# CLK_HMC7044.net
KiCad netlist of a schematic drawn in Altium Designer
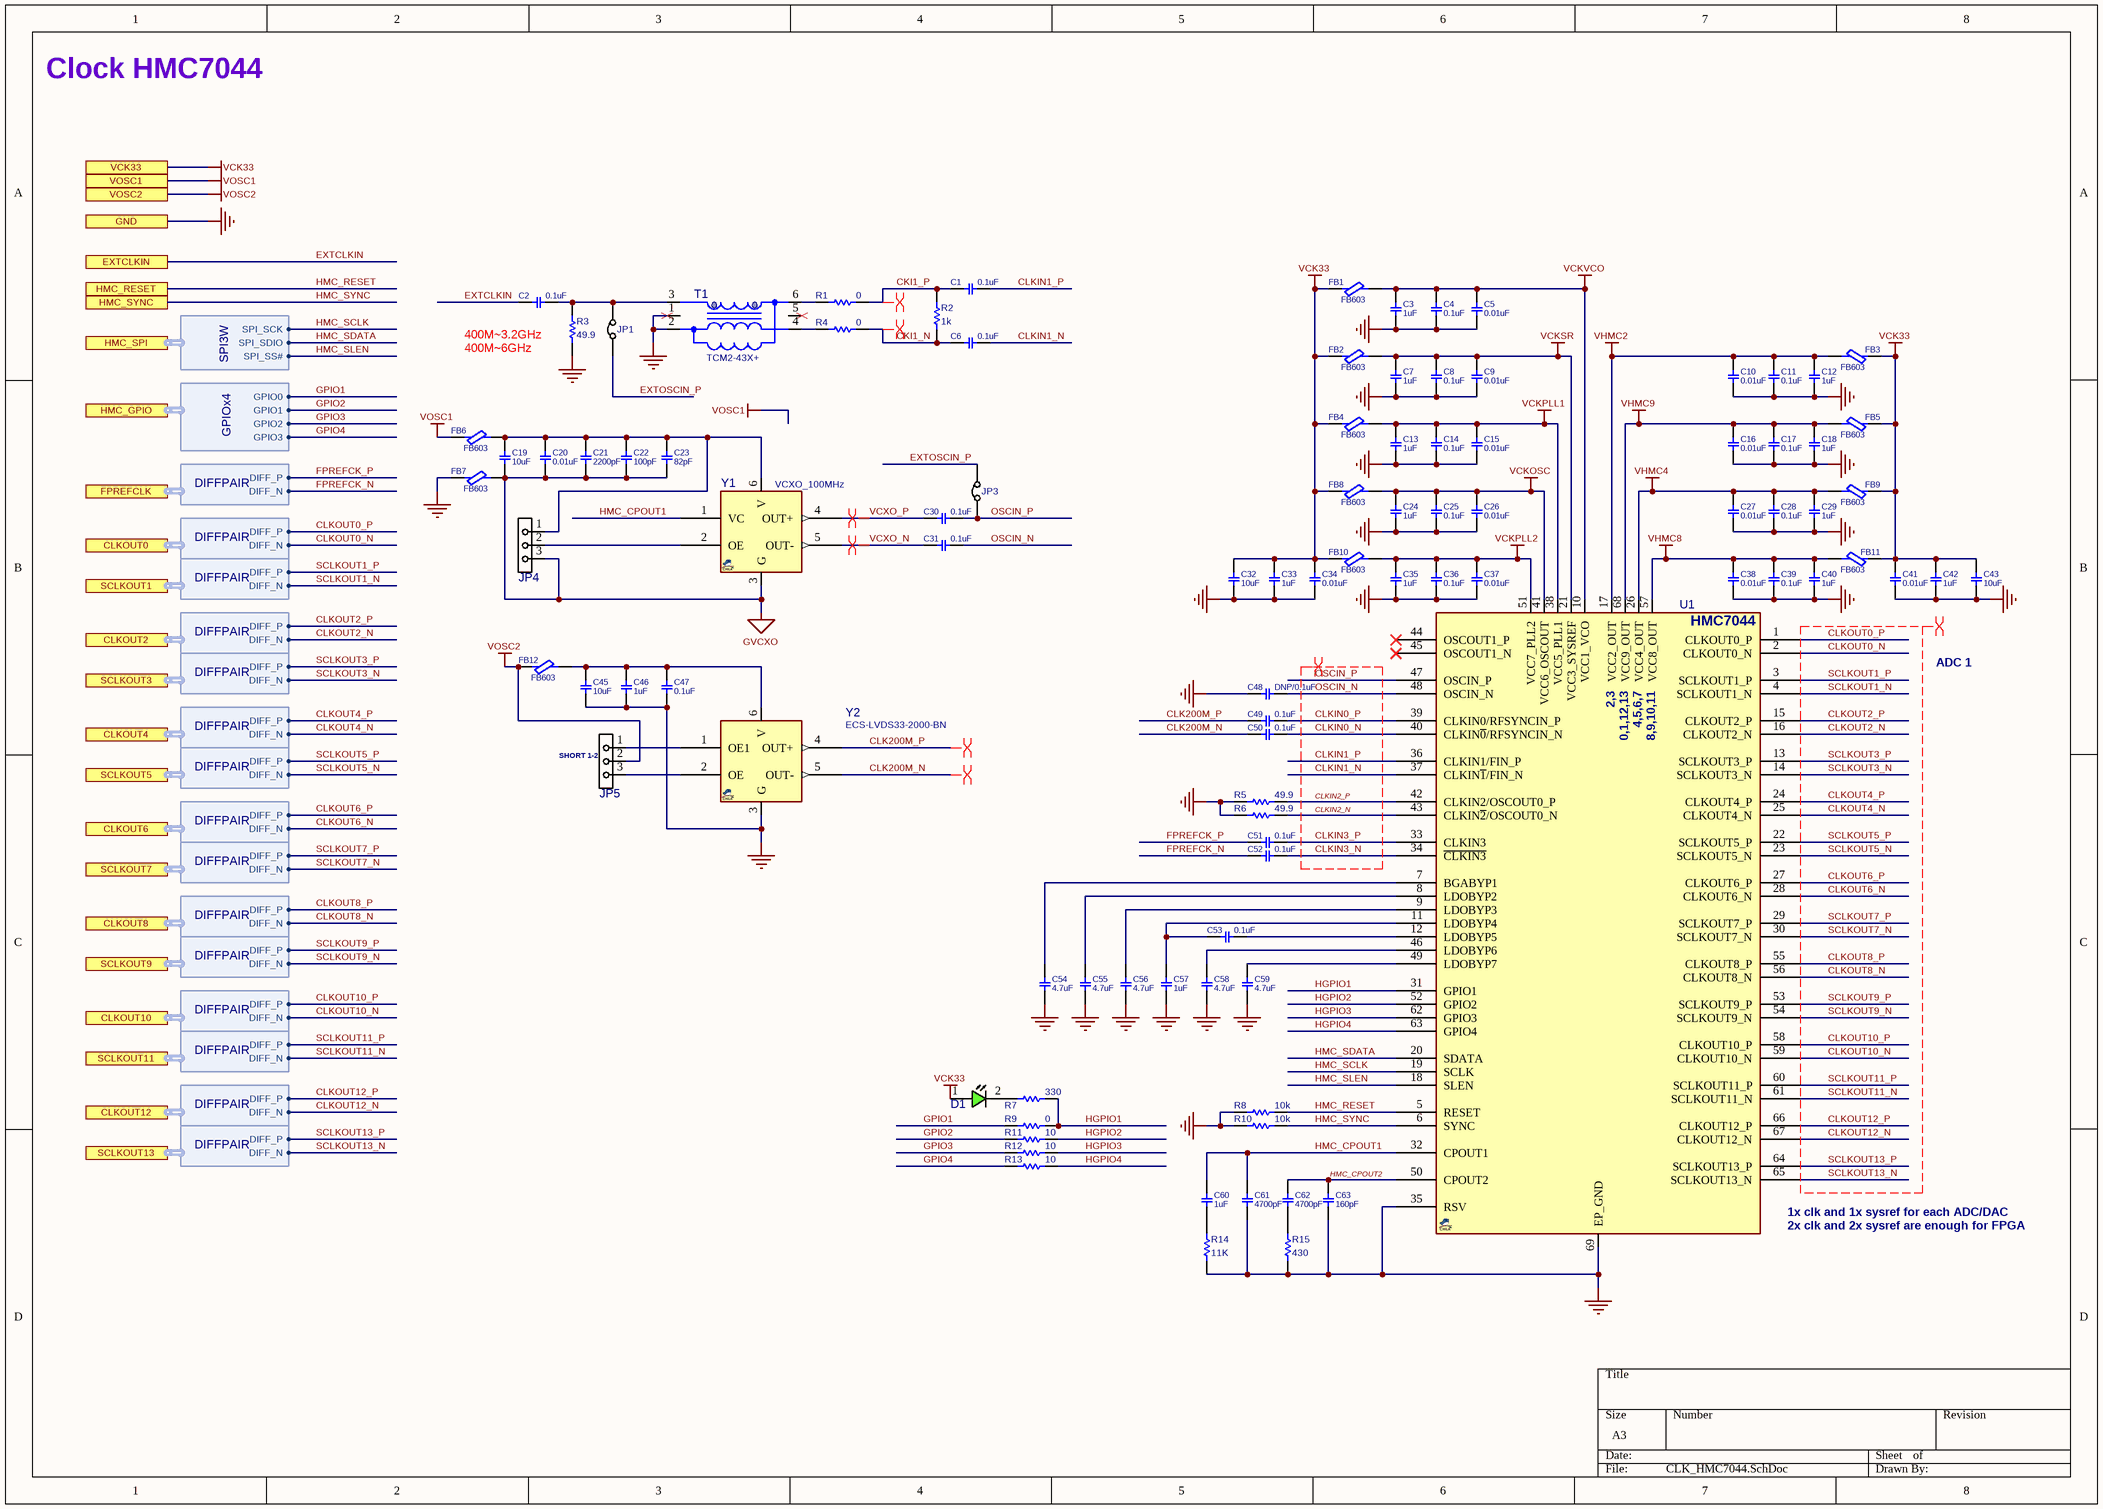
[diagram p0: CLK_HMC7044.SchDoc]

(export (version "E")
  (design (tool "Eeschema 10.0.6"))
  (components
    (comp (ref "C1")
      (value "0.1uF")
      (footprint "C0402")
      (description "CAP, MLCC")
      (libsource (lib "mlcc_smd_passive") (part "CAP_SMD_MLCC_100n50T"))
    )
    (comp (ref "C2")
      (value "0.1uF")
      (footprint "C0402")
      (description "CAP, MLCC")
      (libsource (lib "mlcc_smd_passive") (part "CAP_SMD_MLCC_100n50T"))
    )
    (comp (ref "C3")
      (value "1uF")
      (footprint "C0402")
      (description "CAP, MLCC")
      (libsource (lib "mlcc_smd_passive") (part "CAP_SMD_MLCC_100n50T"))
    )
    (comp (ref "C4")
      (value "0.1uF")
      (footprint "C0402")
      (description "CAP, MLCC")
      (libsource (lib "mlcc_smd_passive") (part "CAP_SMD_MLCC_100n50T"))
    )
    (comp (ref "C5")
      (value "0.01uF")
      (footprint "C0402")
      (description "CAP, MLCC")
      (libsource (lib "mlcc_smd_passive") (part "CAP_SMD_MLCC_100n50T"))
    )
    (comp (ref "C6")
      (value "0.1uF")
      (footprint "C0402")
      (description "CAP, MLCC")
      (libsource (lib "mlcc_smd_passive") (part "CAP_SMD_MLCC_100n50T"))
    )
    (comp (ref "C7")
      (value "1uF")
      (footprint "C0402")
      (description "CAP, MLCC")
      (libsource (lib "mlcc_smd_passive") (part "CAP_SMD_MLCC_100n50T"))
    )
    (comp (ref "C8")
      (value "0.1uF")
      (footprint "C0402")
      (description "CAP, MLCC")
      (libsource (lib "mlcc_smd_passive") (part "CAP_SMD_MLCC_100n50T"))
    )
    (comp (ref "C9")
      (value "0.01uF")
      (footprint "C0402")
      (description "CAP, MLCC")
      (libsource (lib "mlcc_smd_passive") (part "CAP_SMD_MLCC_100n50T"))
    )
    (comp (ref "C10")
      (value "0.01uF")
      (footprint "C0402")
      (description "CAP, MLCC")
      (libsource (lib "mlcc_smd_passive") (part "CAP_SMD_MLCC_100n50T"))
    )
    (comp (ref "C11")
      (value "0.1uF")
      (footprint "C0402")
      (description "CAP, MLCC")
      (libsource (lib "mlcc_smd_passive") (part "CAP_SMD_MLCC_100n50T"))
    )
    (comp (ref "C12")
      (value "1uF")
      (footprint "C0402")
      (description "CAP, MLCC")
      (libsource (lib "mlcc_smd_passive") (part "CAP_SMD_MLCC_100n50T"))
    )
    (comp (ref "C13")
      (value "1uF")
      (footprint "C0402")
      (description "CAP, MLCC")
      (libsource (lib "mlcc_smd_passive") (part "CAP_SMD_MLCC_100n50T"))
    )
    (comp (ref "C14")
      (value "0.1uF")
      (footprint "C0402")
      (description "CAP, MLCC")
      (libsource (lib "mlcc_smd_passive") (part "CAP_SMD_MLCC_100n50T"))
    )
    (comp (ref "C15")
      (value "0.01uF")
      (footprint "C0402")
      (description "CAP, MLCC")
      (libsource (lib "mlcc_smd_passive") (part "CAP_SMD_MLCC_100n50T"))
    )
    (comp (ref "C16")
      (value "0.01uF")
      (footprint "C0402")
      (description "CAP, MLCC")
      (libsource (lib "mlcc_smd_passive") (part "CAP_SMD_MLCC_100n50T"))
    )
    (comp (ref "C17")
      (value "0.1uF")
      (footprint "C0402")
      (description "CAP, MLCC")
      (libsource (lib "mlcc_smd_passive") (part "CAP_SMD_MLCC_100n50T"))
    )
    (comp (ref "C18")
      (value "1uF")
      (footprint "C0402")
      (description "CAP, MLCC")
      (libsource (lib "mlcc_smd_passive") (part "CAP_SMD_MLCC_100n50T"))
    )
    (comp (ref "C19")
      (value "10uF")
      (footprint "C0402")
      (description "CAP, MLCC")
      (libsource (lib "mlcc_smd_passive") (part "CAP_SMD_MLCC_100n50T"))
    )
    (comp (ref "C20")
      (value "0.01uF")
      (footprint "C0402")
      (description "CAP, MLCC")
      (libsource (lib "mlcc_smd_passive") (part "CAP_SMD_MLCC_100n50T"))
    )
    (comp (ref "C21")
      (value "2200pF")
      (footprint "C0402")
      (description "CAP, MLCC")
      (libsource (lib "mlcc_smd_passive") (part "CAP_SMD_MLCC_100n50T"))
    )
    (comp (ref "C22")
      (value "100pF")
      (footprint "C0402")
      (description "CAP, MLCC")
      (libsource (lib "mlcc_smd_passive") (part "CAP_SMD_MLCC_100n50T"))
    )
    (comp (ref "C23")
      (value "82pF")
      (footprint "C0402")
      (description "CAP, MLCC")
      (libsource (lib "mlcc_smd_passive") (part "CAP_SMD_MLCC_100n50T"))
    )
    (comp (ref "C24")
      (value "1uF")
      (footprint "C0402")
      (description "CAP, MLCC")
      (libsource (lib "mlcc_smd_passive") (part "CAP_SMD_MLCC_100n50T"))
    )
    (comp (ref "C25")
      (value "0.1uF")
      (footprint "C0402")
      (description "CAP, MLCC")
      (libsource (lib "mlcc_smd_passive") (part "CAP_SMD_MLCC_100n50T"))
    )
    (comp (ref "C26")
      (value "0.01uF")
      (footprint "C0402")
      (description "CAP, MLCC")
      (libsource (lib "mlcc_smd_passive") (part "CAP_SMD_MLCC_100n50T"))
    )
    (comp (ref "C27")
      (value "0.01uF")
      (footprint "C0402")
      (description "CAP, MLCC")
      (libsource (lib "mlcc_smd_passive") (part "CAP_SMD_MLCC_100n50T"))
    )
    (comp (ref "C28")
      (value "0.1uF")
      (footprint "C0402")
      (description "CAP, MLCC")
      (libsource (lib "mlcc_smd_passive") (part "CAP_SMD_MLCC_100n50T"))
    )
    (comp (ref "C29")
      (value "1uF")
      (footprint "C0402")
      (description "CAP, MLCC")
      (libsource (lib "mlcc_smd_passive") (part "CAP_SMD_MLCC_100n50T"))
    )
    (comp (ref "C30")
      (value "0.1uF")
      (footprint "C0402")
      (description "CAP, MLCC")
      (libsource (lib "mlcc_smd_passive") (part "CAP_SMD_MLCC_100n50T"))
    )
    (comp (ref "C31")
      (value "0.1uF")
      (footprint "C0402")
      (description "CAP, MLCC")
      (libsource (lib "mlcc_smd_passive") (part "CAP_SMD_MLCC_100n50T"))
    )
    (comp (ref "C32")
      (value "10uF")
      (footprint "C0402")
      (description "CAP, MLCC")
      (libsource (lib "mlcc_smd_passive") (part "CAP_SMD_MLCC_100n50T"))
    )
    (comp (ref "C33")
      (value "1uF")
      (footprint "C0402")
      (description "CAP, MLCC")
      (libsource (lib "mlcc_smd_passive") (part "CAP_SMD_MLCC_100n50T"))
    )
    (comp (ref "C34")
      (value "0.01uF")
      (footprint "C0402")
      (description "CAP, MLCC")
      (libsource (lib "mlcc_smd_passive") (part "CAP_SMD_MLCC_100n50T"))
    )
    (comp (ref "C35")
      (value "1uF")
      (footprint "C0402")
      (description "CAP, MLCC")
      (libsource (lib "mlcc_smd_passive") (part "CAP_SMD_MLCC_100n50T"))
    )
    (comp (ref "C36")
      (value "0.1uF")
      (footprint "C0402")
      (description "CAP, MLCC")
      (libsource (lib "mlcc_smd_passive") (part "CAP_SMD_MLCC_100n50T"))
    )
    (comp (ref "C37")
      (value "0.01uF")
      (footprint "C0402")
      (description "CAP, MLCC")
      (libsource (lib "mlcc_smd_passive") (part "CAP_SMD_MLCC_100n50T"))
    )
    (comp (ref "C38")
      (value "0.01uF")
      (footprint "C0402")
      (description "CAP, MLCC")
      (libsource (lib "mlcc_smd_passive") (part "CAP_SMD_MLCC_100n50T"))
    )
    (comp (ref "C39")
      (value "0.1uF")
      (footprint "C0402")
      (description "CAP, MLCC")
      (libsource (lib "mlcc_smd_passive") (part "CAP_SMD_MLCC_100n50T"))
    )
    (comp (ref "C40")
      (value "1uF")
      (footprint "C0402")
      (description "CAP, MLCC")
      (libsource (lib "mlcc_smd_passive") (part "CAP_SMD_MLCC_100n50T"))
    )
    (comp (ref "C41")
      (value "0.01uF")
      (footprint "C0402")
      (description "CAP, MLCC")
      (libsource (lib "mlcc_smd_passive") (part "CAP_SMD_MLCC_100n50T"))
    )
    (comp (ref "C42")
      (value "1uF")
      (footprint "C0402")
      (description "CAP, MLCC")
      (libsource (lib "mlcc_smd_passive") (part "CAP_SMD_MLCC_100n50T"))
    )
    (comp (ref "C43")
      (value "10uF")
      (footprint "C0402")
      (description "CAP, MLCC")
      (libsource (lib "mlcc_smd_passive") (part "CAP_SMD_MLCC_100n50T"))
    )
    (comp (ref "C45")
      (value "10uF")
      (footprint "C0402")
      (description "CAP, MLCC")
      (libsource (lib "mlcc_smd_passive") (part "CAP_SMD_MLCC_100n50T"))
    )
    (comp (ref "C46")
      (value "1uF")
      (footprint "C0402")
      (description "CAP, MLCC")
      (libsource (lib "mlcc_smd_passive") (part "CAP_SMD_MLCC_100n50T"))
    )
    (comp (ref "C47")
      (value "0.1uF")
      (footprint "C0402")
      (description "CAP, MLCC")
      (libsource (lib "mlcc_smd_passive") (part "CAP_SMD_MLCC_100n50T"))
    )
    (comp (ref "C48")
      (value "DNP/0.1uF")
      (footprint "C0402")
      (description "CAP, MLCC")
      (libsource (lib "mlcc_smd_passive") (part "CAP_SMD_MLCC_100n50T"))
    )
    (comp (ref "C49")
      (value "0.1uF")
      (footprint "C0402")
      (description "CAP, MLCC")
      (libsource (lib "mlcc_smd_passive") (part "CAP_SMD_MLCC_100n50T"))
    )
    (comp (ref "C50")
      (value "0.1uF")
      (footprint "C0402")
      (description "CAP, MLCC")
      (libsource (lib "mlcc_smd_passive") (part "CAP_SMD_MLCC_100n50T"))
    )
    (comp (ref "C51")
      (value "0.1uF")
      (footprint "C0402")
      (description "CAP, MLCC")
      (libsource (lib "mlcc_smd_passive") (part "CAP_SMD_MLCC_100n50T"))
    )
    (comp (ref "C52")
      (value "0.1uF")
      (footprint "C0402")
      (description "CAP, MLCC")
      (libsource (lib "mlcc_smd_passive") (part "CAP_SMD_MLCC_100n50T"))
    )
    (comp (ref "C53")
      (value "0.1uF")
      (footprint "C0402")
      (description "CAP, MLCC")
      (libsource (lib "mlcc_smd_passive") (part "CAP_SMD_MLCC_100n50T"))
    )
    (comp (ref "C54")
      (value "4.7uF")
      (footprint "C0402")
      (description "CAP, MLCC")
      (libsource (lib "mlcc_smd_passive") (part "CAP_SMD_MLCC_100n50T"))
    )
    (comp (ref "C55")
      (value "4.7uF")
      (footprint "C0402")
      (description "CAP, MLCC")
      (libsource (lib "mlcc_smd_passive") (part "CAP_SMD_MLCC_100n50T"))
    )
    (comp (ref "C56")
      (value "4.7uF")
      (footprint "C0402")
      (description "CAP, MLCC")
      (libsource (lib "mlcc_smd_passive") (part "CAP_SMD_MLCC_100n50T"))
    )
    (comp (ref "C57")
      (value "1uF")
      (footprint "C0402")
      (description "CAP, MLCC")
      (libsource (lib "mlcc_smd_passive") (part "CAP_SMD_MLCC_100n50T"))
    )
    (comp (ref "C58")
      (value "4.7uF")
      (footprint "C0402")
      (description "CAP, MLCC")
      (libsource (lib "mlcc_smd_passive") (part "CAP_SMD_MLCC_100n50T"))
    )
    (comp (ref "C59")
      (value "4.7uF")
      (footprint "C0402")
      (description "CAP, MLCC")
      (libsource (lib "mlcc_smd_passive") (part "CAP_SMD_MLCC_100n50T"))
    )
    (comp (ref "C60")
      (value "1uF")
      (footprint "C0402")
      (description "CAP, MLCC")
      (libsource (lib "mlcc_smd_passive") (part "CAP_SMD_MLCC_100n50T"))
    )
    (comp (ref "C61")
      (value "4700pF")
      (footprint "C0402")
      (description "CAP, MLCC")
      (libsource (lib "mlcc_smd_passive") (part "CAP_SMD_MLCC_100n50T"))
    )
    (comp (ref "C62")
      (value "4700pF")
      (footprint "C0402")
      (description "CAP, MLCC")
      (libsource (lib "mlcc_smd_passive") (part "CAP_SMD_MLCC_100n50T"))
    )
    (comp (ref "C63")
      (value "160pF")
      (footprint "C0402")
      (description "CAP, MLCC")
      (libsource (lib "mlcc_smd_passive") (part "CAP_SMD_MLCC_100n50T"))
    )
    (comp (ref "D1")
      (value "LED603GRN")
      (footprint "LED0603GRN")
      (description "LED, SMD, 0603, GREEN")
      (fields (field (name "MANF") "Kingbright") (field (name "MANF_P#") "APT1608SGC"))
      (libsource (lib "led(diode)") (part "LED_SMD_0603_GRN"))
    )
    (comp (ref "FB1")
      (value "FB603")
      (footprint "L0603")
      (description "FERRITE_Bead, 0603, 2A, 50mOhm, 120@100MHz")
      (fields (field (name "MANF") "MURATA") (field (name "MANF_P#") "BLM18PG121SN1D"))
      (libsource (lib "emi_filter") (part "FBEAD_SMD_BLM18PG121"))
    )
    (comp (ref "FB2")
      (value "FB603")
      (footprint "L0603")
      (description "FERRITE_Bead, 0603, 2A, 50mOhm, 120@100MHz")
      (fields (field (name "MANF") "MURATA") (field (name "MANF_P#") "BLM18PG121SN1D"))
      (libsource (lib "emi_filter") (part "FBEAD_SMD_BLM18PG121"))
    )
    (comp (ref "FB3")
      (value "FB603")
      (footprint "L0603")
      (description "FERRITE_Bead, 0603, 2A, 50mOhm, 120@100MHz")
      (fields (field (name "MANF") "MURATA") (field (name "MANF_P#") "BLM18PG121SN1D"))
      (libsource (lib "emi_filter") (part "FBEAD_SMD_BLM18PG121"))
    )
    (comp (ref "FB4")
      (value "FB603")
      (footprint "L0603")
      (description "FERRITE_Bead, 0603, 2A, 50mOhm, 120@100MHz")
      (fields (field (name "MANF") "MURATA") (field (name "MANF_P#") "BLM18PG121SN1D"))
      (libsource (lib "emi_filter") (part "FBEAD_SMD_BLM18PG121"))
    )
    (comp (ref "FB5")
      (value "FB603")
      (footprint "L0603")
      (description "FERRITE_Bead, 0603, 2A, 50mOhm, 120@100MHz")
      (fields (field (name "MANF") "MURATA") (field (name "MANF_P#") "BLM18PG121SN1D"))
      (libsource (lib "emi_filter") (part "FBEAD_SMD_BLM18PG121"))
    )
    (comp (ref "FB6")
      (value "FB603")
      (footprint "L0603")
      (description "FERRITE_Bead, 0603, 2A, 50mOhm, 120@100MHz")
      (fields (field (name "MANF") "MURATA") (field (name "MANF_P#") "BLM18PG121SN1D"))
      (libsource (lib "emi_filter") (part "FBEAD_SMD_BLM18PG121"))
    )
    (comp (ref "FB7")
      (value "FB603")
      (footprint "L0603")
      (description "FERRITE_Bead, 0603, 2A, 50mOhm, 120@100MHz")
      (fields (field (name "MANF") "MURATA") (field (name "MANF_P#") "BLM18PG121SN1D"))
      (libsource (lib "emi_filter") (part "FBEAD_SMD_BLM18PG121"))
    )
    (comp (ref "FB8")
      (value "FB603")
      (footprint "L0603")
      (description "FERRITE_Bead, 0603, 2A, 50mOhm, 120@100MHz")
      (fields (field (name "MANF") "MURATA") (field (name "MANF_P#") "BLM18PG121SN1D"))
      (libsource (lib "emi_filter") (part "FBEAD_SMD_BLM18PG121"))
    )
    (comp (ref "FB9")
      (value "FB603")
      (footprint "L0603")
      (description "FERRITE_Bead, 0603, 2A, 50mOhm, 120@100MHz")
      (fields (field (name "MANF") "MURATA") (field (name "MANF_P#") "BLM18PG121SN1D"))
      (libsource (lib "emi_filter") (part "FBEAD_SMD_BLM18PG121"))
    )
    (comp (ref "FB10")
      (value "FB603")
      (footprint "L0603")
      (description "FERRITE_Bead, 0603, 2A, 50mOhm, 120@100MHz")
      (fields (field (name "MANF") "MURATA") (field (name "MANF_P#") "BLM18PG121SN1D"))
      (libsource (lib "emi_filter") (part "FBEAD_SMD_BLM18PG121"))
    )
    (comp (ref "FB11")
      (value "FB603")
      (footprint "L0603")
      (description "FERRITE_Bead, 0603, 2A, 50mOhm, 120@100MHz")
      (fields (field (name "MANF") "MURATA") (field (name "MANF_P#") "BLM18PG121SN1D"))
      (libsource (lib "emi_filter") (part "FBEAD_SMD_BLM18PG121"))
    )
    (comp (ref "FB12")
      (value "FB603")
      (footprint "L0603")
      (description "FERRITE_Bead, 0603, 2A, 50mOhm, 120@100MHz")
      (fields (field (name "MANF") "MURATA") (field (name "MANF_P#") "BLM18PG121SN1D"))
      (libsource (lib "emi_filter") (part "FBEAD_SMD_BLM18PG121"))
    )
    (comp (ref "JP1")
      (value "JMPSOLDER")
      (footprint "JP_40X50")
      (description "JUMPER,  solder")
      (fields (field (name "MANF") "MANF") (field (name "MANF_P#") "MANF_P#"))
      (libsource (lib "test-tp_jumper") (part "JUMPER_SOLDER"))
    )
    (comp (ref "JP3")
      (value "JMPSOLDER")
      (footprint "JP_40X50")
      (description "JUMPER,  solder")
      (fields (field (name "MANF") "MANF") (field (name "MANF_P#") "MANF_P#"))
      (libsource (lib "test-tp_jumper") (part "JUMPER_SOLDER"))
    )
    (comp (ref "JP4")
      (value "JMPHDR3PIN")
      (footprint "JP_3_40X90")
      (description "JUMPER, HEADER 3PIN")
      (fields (field (name "MANF") "MANF") (field (name "MANF_P#") "MANF_P#"))
      (libsource (lib "test-tp_jumper") (part "JUMPER_SOLDER_3P"))
    )
    (comp (ref "JP5")
      (value "JMPHDR3PIN")
      (footprint "JP_3_40X90")
      (description "JUMPER, HEADER 3PIN")
      (fields (field (name "MANF") "MANF") (field (name "MANF_P#") "MANF_P#"))
      (libsource (lib "test-tp_jumper") (part "JUMPER_SOLDER_3P"))
    )
    (comp (ref "R1")
      (value "0")
      (footprint "R0402")
      (description "Resistor")
      (libsource (lib "SPassive") (part "Res"))
    )
    (comp (ref "R2")
      (value "1k")
      (footprint "R0402")
      (description "Resistor")
      (libsource (lib "SPassive") (part "Res"))
    )
    (comp (ref "R3")
      (value "49.9")
      (footprint "R0402")
      (description "Resistor")
      (libsource (lib "SPassive") (part "Res"))
    )
    (comp (ref "R4")
      (value "0")
      (footprint "R0402")
      (description "Resistor")
      (libsource (lib "SPassive") (part "Res"))
    )
    (comp (ref "R5")
      (value "49.9")
      (footprint "R0402")
      (description "Resistor")
      (libsource (lib "SPassive") (part "Res"))
    )
    (comp (ref "R6")
      (value "49.9")
      (footprint "R0402")
      (description "Resistor")
      (libsource (lib "SPassive") (part "Res"))
    )
    (comp (ref "R7")
      (value "330")
      (footprint "R0402")
      (description "Resistor")
      (libsource (lib "SPassive") (part "Res"))
    )
    (comp (ref "R8")
      (value "10k")
      (footprint "R0402")
      (description "Resistor")
      (libsource (lib "SPassive") (part "Res"))
    )
    (comp (ref "R9")
      (value "0")
      (footprint "R0402")
      (description "RESISTOR, SMD")
      (libsource (lib "passive_smd") (part "RES_SMD_0402"))
    )
    (comp (ref "R10")
      (value "10k")
      (footprint "R0402")
      (description "Resistor")
      (libsource (lib "SPassive") (part "Res"))
    )
    (comp (ref "R11")
      (value "10")
      (footprint "R0402")
      (description "RESISTOR, SMD")
      (libsource (lib "passive_smd") (part "RES_SMD_0402"))
    )
    (comp (ref "R12")
      (value "10")
      (footprint "R0402")
      (description "RESISTOR, SMD")
      (libsource (lib "passive_smd") (part "RES_SMD_0402"))
    )
    (comp (ref "R13")
      (value "10")
      (footprint "R0402")
      (description "RESISTOR, SMD")
      (libsource (lib "passive_smd") (part "RES_SMD_0402"))
    )
    (comp (ref "R14")
      (value "11K")
      (footprint "R0402")
      (description "Resistor")
      (libsource (lib "SPassive") (part "Res"))
    )
    (comp (ref "R15")
      (value "430")
      (footprint "R0402")
      (description "Resistor")
      (libsource (lib "SPassive") (part "Res"))
    )
    (comp (ref "T1")
      (value "TCM2-43X+")
      (footprint "TRNS127_6_S380CW")
      (description "RF Transformer, 1:2, 50Ohm, 10~4000MHz")
      (fields (field (name "MANF") "Mini-Circuit"))
      (libsource (lib "transformer_rf") (part "TCM2-43X+"))
    )
    (comp (ref "U1")
      (value "HMC7044")
      (footprint "QFN50_68T")
      (description "Clock Synthesizer / Jitter Cleaner HiPerf,3.2 GHz,14-OP Jttr Att w/JESD204B")
      (fields (field (name "MANF") "Analog Devices") (field (name "MANF_P#") "HMC7044LP10BE"))
      (libsource (lib "clockic") (part "HMC7044_QFN68"))
    )
    (comp (ref "Y1")
      (value "VCXO_100MHz")
      (footprint "XTL_6_9X14")
      (description "CLOCK OSCILLATOR,")
      (fields (field (name "MANF") "CRYSTEK") (field (name "MANF_P#") "CVPD-920X-100"))
      (libsource (lib "crystal_osc") (part "OSC_6_CVPD-920-100M"))
    )
    (comp (ref "Y2")
      (value "ECS-LVDS33-2000-BN")
      (footprint "XTL_6_7050")
      (description "CLOCK OSCILLATOR, DIFFERENTIAL, 200MHZ")
      (fields (field (name "MANF") "SiTime") (field (name "MANF_P#") "SIT9102AI-243N25E200.0000"))
      (libsource (lib "crystal_osc") (part "OSC_6_SIT9102_200MHz"))
    )
  )
  (nets
    (net (code "4") (name "/CKI1_N") (class "Default")
      (node (ref "C6") (pin "1") (pinfunction "1_1") (pintype "passive"))
      (node (ref "R2") (pin "1") (pinfunction "1_1") (pintype "passive"))
      (node (ref "R4") (pin "1") (pinfunction "1_1") (pintype "passive"))
    )
    (net (code "5") (name "/CKI1_P") (class "Default")
      (node (ref "C1") (pin "1") (pinfunction "1_1") (pintype "passive"))
      (node (ref "R1") (pin "1") (pinfunction "1_1") (pintype "passive"))
      (node (ref "R2") (pin "2") (pinfunction "2_2") (pintype "passive"))
    )
    (net (code "6") (name "/CLK200M_N") (class "Default")
      (node (ref "C50") (pin "1") (pinfunction "1_1") (pintype "passive"))
      (node (ref "Y2") (pin "5") (pinfunction "OUT-_5") (pintype "output"))
    )
    (net (code "7") (name "/CLK200M_P") (class "Default")
      (node (ref "C49") (pin "1") (pinfunction "1_1") (pintype "passive"))
      (node (ref "Y2") (pin "4") (pinfunction "OUT+_4") (pintype "output"))
    )
    (net (code "8") (name "/CLKIN0_N") (class "Default")
      (node (ref "C50") (pin "2") (pinfunction "2_2") (pintype "passive"))
      (node (ref "U1") (pin "40") (pinfunction "CLKIN~{0}/RFSYNCIN_N_40") (pintype "passive"))
    )
    (net (code "9") (name "/CLKIN0_P") (class "Default")
      (node (ref "C49") (pin "2") (pinfunction "2_2") (pintype "passive"))
      (node (ref "U1") (pin "39") (pinfunction "CLKIN0/RFSYNCIN_P_39") (pintype "passive"))
    )
    (net (code "10") (name "/CLKIN1_N") (class "Default")
      (node (ref "C6") (pin "2") (pinfunction "2_2") (pintype "passive"))
      (node (ref "U1") (pin "37") (pinfunction "CLKIN~{1}/FIN_N_37") (pintype "passive"))
    )
    (net (code "11") (name "/CLKIN1_P") (class "Default")
      (node (ref "C1") (pin "2") (pinfunction "2_2") (pintype "passive"))
      (node (ref "U1") (pin "36") (pinfunction "CLKIN1/FIN_P_36") (pintype "passive"))
    )
    (net (code "12") (name "/CLKIN2_N") (class "Default")
      (node (ref "R6") (pin "1") (pinfunction "1_1") (pintype "passive"))
      (node (ref "U1") (pin "43") (pinfunction "CLKIN~{2}/OSCOUT0_N_43") (pintype "passive"))
    )
    (net (code "13") (name "/CLKIN2_P") (class "Default")
      (node (ref "R5") (pin "1") (pinfunction "1_1") (pintype "passive"))
      (node (ref "U1") (pin "42") (pinfunction "CLKIN2/OSCOUT0_P_42") (pintype "passive"))
    )
    (net (code "14") (name "/CLKIN3_N") (class "Default")
      (node (ref "C52") (pin "2") (pinfunction "2_2") (pintype "passive"))
      (node (ref "U1") (pin "34") (pinfunction "CLKIN3_34") (pintype "passive"))
    )
    (net (code "15") (name "/CLKIN3_P") (class "Default")
      (node (ref "C51") (pin "2") (pinfunction "2_2") (pintype "passive"))
      (node (ref "U1") (pin "33") (pinfunction "CLKIN3_33") (pintype "passive"))
    )
    (net (code "16") (name "/CLKOUT0_N") (class "Default")
      (node (ref "U1") (pin "2") (pinfunction "CLKOUT0_N_2") (pintype "passive"))
    )
    (net (code "17") (name "/CLKOUT0_P") (class "Default")
      (node (ref "U1") (pin "1") (pinfunction "CLKOUT0_P_1") (pintype "passive"))
    )
    (net (code "18") (name "/CLKOUT2_N") (class "Default")
      (node (ref "U1") (pin "16") (pinfunction "CLKOUT2_N_16") (pintype "passive"))
    )
    (net (code "19") (name "/CLKOUT2_P") (class "Default")
      (node (ref "U1") (pin "15") (pinfunction "CLKOUT2_P_15") (pintype "passive"))
    )
    (net (code "20") (name "/CLKOUT4_N") (class "Default")
      (node (ref "U1") (pin "25") (pinfunction "CLKOUT4_N_25") (pintype "passive"))
    )
    (net (code "21") (name "/CLKOUT4_P") (class "Default")
      (node (ref "U1") (pin "24") (pinfunction "CLKOUT4_P_24") (pintype "passive"))
    )
    (net (code "22") (name "/CLKOUT6_N") (class "Default")
      (node (ref "U1") (pin "28") (pinfunction "CLKOUT6_N_28") (pintype "passive"))
    )
    (net (code "23") (name "/CLKOUT6_P") (class "Default")
      (node (ref "U1") (pin "27") (pinfunction "CLKOUT6_P_27") (pintype "passive"))
    )
    (net (code "24") (name "/CLKOUT8_N") (class "Default")
      (node (ref "U1") (pin "56") (pinfunction "CLKOUT8_N_56") (pintype "passive"))
    )
    (net (code "25") (name "/CLKOUT8_P") (class "Default")
      (node (ref "U1") (pin "55") (pinfunction "CLKOUT8_P_55") (pintype "passive"))
    )
    (net (code "26") (name "/CLKOUT10_N") (class "Default")
      (node (ref "U1") (pin "59") (pinfunction "CLKOUT10_N_59") (pintype "passive"))
    )
    (net (code "27") (name "/CLKOUT10_P") (class "Default")
      (node (ref "U1") (pin "58") (pinfunction "CLKOUT10_P_58") (pintype "passive"))
    )
    (net (code "28") (name "/CLKOUT12_N") (class "Default")
      (node (ref "U1") (pin "67") (pinfunction "CLKOUT12_N_67") (pintype "passive"))
    )
    (net (code "29") (name "/CLKOUT12_P") (class "Default")
      (node (ref "U1") (pin "66") (pinfunction "CLKOUT12_P_66") (pintype "passive"))
    )
    (net (code "30") (name "/EXTCLKIN") (class "Default")
      (node (ref "C2") (pin "1") (pinfunction "1_1") (pintype "passive"))
    )
    (net (code "31") (name "/EXTOSCIN_P") (class "Default")
      (node (ref "JP1") (pin "1") (pinfunction "1_1") (pintype "passive"))
      (node (ref "JP3") (pin "2") (pinfunction "2_2") (pintype "passive"))
    )
    (net (code "32") (name "/FPREFCK_N") (class "Default")
      (node (ref "C52") (pin "1") (pinfunction "1_1") (pintype "passive"))
    )
    (net (code "33") (name "/FPREFCK_P") (class "Default")
      (node (ref "C51") (pin "1") (pinfunction "1_1") (pintype "passive"))
    )
    (net (code "34") (name "/GPIO1") (class "Default")
      (node (ref "R9") (pin "2") (pinfunction "2_2") (pintype "passive"))
    )
    (net (code "35") (name "/GPIO2") (class "Default")
      (node (ref "R11") (pin "2") (pinfunction "2_2") (pintype "passive"))
    )
    (net (code "36") (name "/GPIO3") (class "Default")
      (node (ref "R12") (pin "2") (pinfunction "2_2") (pintype "passive"))
    )
    (net (code "37") (name "/GPIO4") (class "Default")
      (node (ref "R13") (pin "2") (pinfunction "2_2") (pintype "passive"))
    )
    (net (code "38") (name "/HGPIO1") (class "Default")
      (node (ref "R7") (pin "2") (pinfunction "2_2") (pintype "passive"))
      (node (ref "R9") (pin "1") (pinfunction "1_1") (pintype "passive"))
      (node (ref "U1") (pin "31") (pinfunction "GPIO1_31") (pintype "passive"))
    )
    (net (code "39") (name "/HGPIO2") (class "Default")
      (node (ref "R11") (pin "1") (pinfunction "1_1") (pintype "passive"))
      (node (ref "U1") (pin "52") (pinfunction "GPIO2_52") (pintype "passive"))
    )
    (net (code "40") (name "/HGPIO3") (class "Default")
      (node (ref "R12") (pin "1") (pinfunction "1_1") (pintype "passive"))
      (node (ref "U1") (pin "62") (pinfunction "GPIO3_62") (pintype "passive"))
    )
    (net (code "41") (name "/HGPIO4") (class "Default")
      (node (ref "R13") (pin "1") (pinfunction "1_1") (pintype "passive"))
      (node (ref "U1") (pin "63") (pinfunction "GPIO4_63") (pintype "passive"))
    )
    (net (code "42") (name "/HMC_CPOUT1") (class "Default")
      (node (ref "C60") (pin "1") (pinfunction "1_1") (pintype "passive"))
      (node (ref "C61") (pin "2") (pinfunction "2_2") (pintype "passive"))
      (node (ref "U1") (pin "32") (pinfunction "CPOUT1_32") (pintype "passive"))
      (node (ref "Y1") (pin "1") (pinfunction "VC_1") (pintype "passive"))
    )
    (net (code "43") (name "/HMC_CPOUT2") (class "Default")
      (node (ref "C62") (pin "2") (pinfunction "2_2") (pintype "passive"))
      (node (ref "C63") (pin "2") (pinfunction "2_2") (pintype "passive"))
      (node (ref "U1") (pin "50") (pinfunction "CPOUT2_50") (pintype "passive"))
    )
    (net (code "44") (name "/HMC_RESET") (class "Default")
      (node (ref "R8") (pin "2") (pinfunction "2_2") (pintype "passive"))
      (node (ref "U1") (pin "5") (pinfunction "RESET_5") (pintype "passive"))
    )
    (net (code "45") (name "/HMC_SCLK") (class "Default")
      (node (ref "U1") (pin "19") (pinfunction "SCLK_19") (pintype "passive"))
    )
    (net (code "46") (name "/HMC_SDATA") (class "Default")
      (node (ref "U1") (pin "20") (pinfunction "SDATA_20") (pintype "passive"))
    )
    (net (code "47") (name "/HMC_SLEN") (class "Default")
      (node (ref "U1") (pin "18") (pinfunction "SLEN_18") (pintype "passive"))
    )
    (net (code "48") (name "/HMC_SYNC") (class "Default")
      (node (ref "R10") (pin "2") (pinfunction "2_2") (pintype "passive"))
      (node (ref "U1") (pin "6") (pinfunction "SYNC_6") (pintype "passive"))
    )
    (net (code "49") (name "/OSCIN_N") (class "Default")
      (node (ref "C31") (pin "2") (pinfunction "2_2") (pintype "passive"))
      (node (ref "C48") (pin "2") (pinfunction "2_2") (pintype "passive"))
      (node (ref "U1") (pin "48") (pinfunction "OSCIN_N_48") (pintype "passive"))
    )
    (net (code "50") (name "/OSCIN_P") (class "Default")
      (node (ref "C30") (pin "2") (pinfunction "2_2") (pintype "passive"))
      (node (ref "JP3") (pin "1") (pinfunction "1_1") (pintype "passive"))
      (node (ref "U1") (pin "47") (pinfunction "OSCIN_P_47") (pintype "passive"))
    )
    (net (code "51") (name "/SCLKOUT1_N") (class "Default")
      (node (ref "U1") (pin "4") (pinfunction "SCLKOUT1_N_4") (pintype "passive"))
    )
    (net (code "52") (name "/SCLKOUT1_P") (class "Default")
      (node (ref "U1") (pin "3") (pinfunction "SCLKOUT1_P_3") (pintype "passive"))
    )
    (net (code "53") (name "/SCLKOUT3_N") (class "Default")
      (node (ref "U1") (pin "14") (pinfunction "SCLKOUT3_N_14") (pintype "passive"))
    )
    (net (code "54") (name "/SCLKOUT3_P") (class "Default")
      (node (ref "U1") (pin "13") (pinfunction "SCLKOUT3_P_13") (pintype "passive"))
    )
    (net (code "55") (name "/SCLKOUT5_N") (class "Default")
      (node (ref "U1") (pin "23") (pinfunction "SCLKOUT5_N_23") (pintype "passive"))
    )
    (net (code "56") (name "/SCLKOUT5_P") (class "Default")
      (node (ref "U1") (pin "22") (pinfunction "SCLKOUT5_P_22") (pintype "passive"))
    )
    (net (code "57") (name "/SCLKOUT7_N") (class "Default")
      (node (ref "U1") (pin "30") (pinfunction "SCLKOUT7_N_30") (pintype "passive"))
    )
    (net (code "58") (name "/SCLKOUT7_P") (class "Default")
      (node (ref "U1") (pin "29") (pinfunction "SCLKOUT7_P_29") (pintype "passive"))
    )
    (net (code "59") (name "/SCLKOUT9_N") (class "Default")
      (node (ref "U1") (pin "54") (pinfunction "SCLKOUT9_N_54") (pintype "passive"))
    )
    (net (code "60") (name "/SCLKOUT9_P") (class "Default")
      (node (ref "U1") (pin "53") (pinfunction "SCLKOUT9_P_53") (pintype "passive"))
    )
    (net (code "61") (name "/SCLKOUT11_N") (class "Default")
      (node (ref "U1") (pin "61") (pinfunction "SCLKOUT11_N_61") (pintype "passive"))
    )
    (net (code "62") (name "/SCLKOUT11_P") (class "Default")
      (node (ref "U1") (pin "60") (pinfunction "SCLKOUT11_P_60") (pintype "passive"))
    )
    (net (code "63") (name "/SCLKOUT13_N") (class "Default")
      (node (ref "U1") (pin "65") (pinfunction "SCLKOUT13_N_65") (pintype "passive"))
    )
    (net (code "64") (name "/SCLKOUT13_P") (class "Default")
      (node (ref "U1") (pin "64") (pinfunction "SCLKOUT13_P_64") (pintype "passive"))
    )
    (net (code "65") (name "/VCXO_N") (class "Default")
      (node (ref "C31") (pin "1") (pinfunction "1_1") (pintype "passive"))
      (node (ref "Y1") (pin "5") (pinfunction "OUT-_5") (pintype "output"))
    )
    (net (code "66") (name "/VCXO_P") (class "Default")
      (node (ref "C30") (pin "1") (pinfunction "1_1") (pintype "passive"))
      (node (ref "Y1") (pin "4") (pinfunction "OUT+_4") (pintype "output"))
    )
    (net (code "70") (name "GND") (class "Default")
      (node (ref "C10") (pin "2") (pinfunction "2_2") (pintype "passive"))
      (node (ref "C11") (pin "2") (pinfunction "2_2") (pintype "passive"))
      (node (ref "C12") (pin "2") (pinfunction "2_2") (pintype "passive"))
      (node (ref "C13") (pin "2") (pinfunction "2_2") (pintype "passive"))
      (node (ref "C14") (pin "2") (pinfunction "2_2") (pintype "passive"))
      (node (ref "C15") (pin "2") (pinfunction "2_2") (pintype "passive"))
      (node (ref "C16") (pin "2") (pinfunction "2_2") (pintype "passive"))
      (node (ref "C17") (pin "2") (pinfunction "2_2") (pintype "passive"))
      (node (ref "C18") (pin "2") (pinfunction "2_2") (pintype "passive"))
      (node (ref "C24") (pin "2") (pinfunction "2_2") (pintype "passive"))
      (node (ref "C25") (pin "2") (pinfunction "2_2") (pintype "passive"))
      (node (ref "C26") (pin "2") (pinfunction "2_2") (pintype "passive"))
      (node (ref "C27") (pin "2") (pinfunction "2_2") (pintype "passive"))
      (node (ref "C28") (pin "2") (pinfunction "2_2") (pintype "passive"))
      (node (ref "C29") (pin "2") (pinfunction "2_2") (pintype "passive"))
      (node (ref "C3") (pin "2") (pinfunction "2_2") (pintype "passive"))
      (node (ref "C32") (pin "2") (pinfunction "2_2") (pintype "passive"))
      (node (ref "C33") (pin "2") (pinfunction "2_2") (pintype "passive"))
      (node (ref "C34") (pin "2") (pinfunction "2_2") (pintype "passive"))
      (node (ref "C35") (pin "2") (pinfunction "2_2") (pintype "passive"))
      (node (ref "C36") (pin "2") (pinfunction "2_2") (pintype "passive"))
      (node (ref "C37") (pin "2") (pinfunction "2_2") (pintype "passive"))
      (node (ref "C38") (pin "2") (pinfunction "2_2") (pintype "passive"))
      (node (ref "C39") (pin "2") (pinfunction "2_2") (pintype "passive"))
      (node (ref "C4") (pin "2") (pinfunction "2_2") (pintype "passive"))
      (node (ref "C40") (pin "2") (pinfunction "2_2") (pintype "passive"))
      (node (ref "C41") (pin "2") (pinfunction "2_2") (pintype "passive"))
      (node (ref "C42") (pin "2") (pinfunction "2_2") (pintype "passive"))
      (node (ref "C43") (pin "2") (pinfunction "2_2") (pintype "passive"))
      (node (ref "C45") (pin "2") (pinfunction "2_2") (pintype "passive"))
      (node (ref "C46") (pin "2") (pinfunction "2_2") (pintype "passive"))
      (node (ref "C47") (pin "1") (pinfunction "1_1") (pintype "passive"))
      (node (ref "C48") (pin "1") (pinfunction "1_1") (pintype "passive"))
      (node (ref "C5") (pin "2") (pinfunction "2_2") (pintype "passive"))
      (node (ref "C54") (pin "2") (pinfunction "2_2") (pintype "passive"))
      (node (ref "C55") (pin "2") (pinfunction "2_2") (pintype "passive"))
      (node (ref "C56") (pin "2") (pinfunction "2_2") (pintype "passive"))
      (node (ref "C57") (pin "2") (pinfunction "2_2") (pintype "passive"))
      (node (ref "C58") (pin "2") (pinfunction "2_2") (pintype "passive"))
      (node (ref "C59") (pin "2") (pinfunction "2_2") (pintype "passive"))
      (node (ref "C61") (pin "1") (pinfunction "1_1") (pintype "passive"))
      (node (ref "C63") (pin "1") (pinfunction "1_1") (pintype "passive"))
      (node (ref "C7") (pin "2") (pinfunction "2_2") (pintype "passive"))
      (node (ref "C8") (pin "2") (pinfunction "2_2") (pintype "passive"))
      (node (ref "C9") (pin "2") (pinfunction "2_2") (pintype "passive"))
      (node (ref "FB7") (pin "1") (pinfunction "1_1") (pintype "passive"))
      (node (ref "R10") (pin "1") (pinfunction "1_1") (pintype "passive"))
      (node (ref "R14") (pin "1") (pinfunction "1_1") (pintype "passive"))
      (node (ref "R15") (pin "1") (pinfunction "1_1") (pintype "passive"))
      (node (ref "R3") (pin "1") (pinfunction "1_1") (pintype "passive"))
      (node (ref "R5") (pin "2") (pinfunction "2_2") (pintype "passive"))
      (node (ref "R6") (pin "2") (pinfunction "2_2") (pintype "passive"))
      (node (ref "R8") (pin "1") (pinfunction "1_1") (pintype "passive"))
      (node (ref "T1") (pin "1") (pinfunction "NC_1") (pintype "passive"))
      (node (ref "T1") (pin "2") (pinfunction "PRI_2") (pintype "passive"))
      (node (ref "U1") (pin "35") (pinfunction "RSV_35") (pintype "passive"))
      (node (ref "U1") (pin "69") (pinfunction "EP_GND_69") (pintype "passive"))
      (node (ref "Y2") (pin "3") (pinfunction "G_3") (pintype "power_in"))
    )
    (net (code "71") (name "GVCXO") (class "Default")
      (node (ref "C19") (pin "2") (pinfunction "2_2") (pintype "passive"))
      (node (ref "C20") (pin "1") (pinfunction "1_1") (pintype "passive"))
      (node (ref "C21") (pin "1") (pinfunction "1_1") (pintype "passive"))
      (node (ref "C22") (pin "1") (pinfunction "1_1") (pintype "passive"))
      (node (ref "C23") (pin "1") (pinfunction "1_1") (pintype "passive"))
      (node (ref "FB7") (pin "2") (pinfunction "2_2") (pintype "passive"))
      (node (ref "JP4") (pin "3") (pinfunction "3_3") (pintype "passive"))
      (node (ref "Y1") (pin "3") (pinfunction "G_3") (pintype "power_in"))
    )
    (net (code "72") (name "Net-(C60-Pad2)") (class "Default")
      (node (ref "C60") (pin "2") (pinfunction "2_2") (pintype "passive"))
      (node (ref "R14") (pin "2") (pinfunction "2_2") (pintype "passive"))
    )
    (net (code "73") (name "Net-(C62-Pad1)") (class "Default")
      (node (ref "C62") (pin "1") (pinfunction "1_1") (pintype "passive"))
      (node (ref "R15") (pin "2") (pinfunction "2_2") (pintype "passive"))
    )
    (net (code "74") (name "Net-(D1-CATHODE)") (class "Default")
      (node (ref "D1") (pin "2") (pinfunction "CATHODE_2") (pintype "passive"))
      (node (ref "R7") (pin "1") (pinfunction "1_1") (pintype "passive"))
    )
    (net (code "75") (name "Net-(T1-PRI.)") (class "Default")
      (node (ref "C2") (pin "2") (pinfunction "2_2") (pintype "passive"))
      (node (ref "JP1") (pin "2") (pinfunction "2_2") (pintype "passive"))
      (node (ref "R3") (pin "2") (pinfunction "2_2") (pintype "passive"))
      (node (ref "T1") (pin "3") (pinfunction "PRI._3") (pintype "passive"))
    )
    (net (code "76") (name "Net-(T1-SEC)") (class "Default")
      (node (ref "R4") (pin "2") (pinfunction "2_2") (pintype "passive"))
      (node (ref "T1") (pin "4") (pinfunction "SEC_4") (pintype "passive"))
    )
    (net (code "77") (name "Net-(T1-SEC.)") (class "Default")
      (node (ref "R1") (pin "2") (pinfunction "2_2") (pintype "passive"))
      (node (ref "T1") (pin "6") (pinfunction "SEC._6") (pintype "passive"))
    )
    (net (code "78") (name "Net-(U1-BGABYP1)") (class "Default")
      (node (ref "C54") (pin "1") (pinfunction "1_1") (pintype "passive"))
      (node (ref "U1") (pin "7") (pinfunction "BGABYP1_7") (pintype "passive"))
    )
    (net (code "79") (name "Net-(U1-LDOBYP2)") (class "Default")
      (node (ref "C55") (pin "1") (pinfunction "1_1") (pintype "passive"))
      (node (ref "U1") (pin "8") (pinfunction "LDOBYP2_8") (pintype "passive"))
    )
    (net (code "80") (name "Net-(U1-LDOBYP3)") (class "Default")
      (node (ref "C56") (pin "1") (pinfunction "1_1") (pintype "passive"))
      (node (ref "U1") (pin "9") (pinfunction "LDOBYP3_9") (pintype "passive"))
    )
    (net (code "81") (name "Net-(U1-LDOBYP4)") (class "Default")
      (node (ref "C53") (pin "1") (pinfunction "1_1") (pintype "passive"))
      (node (ref "C57") (pin "1") (pinfunction "1_1") (pintype "passive"))
      (node (ref "U1") (pin "11") (pinfunction "LDOBYP4_11") (pintype "passive"))
    )
    (net (code "82") (name "Net-(U1-LDOBYP5)") (class "Default")
      (node (ref "C53") (pin "2") (pinfunction "2_2") (pintype "passive"))
      (node (ref "U1") (pin "12") (pinfunction "LDOBYP5_12") (pintype "passive"))
    )
    (net (code "83") (name "Net-(U1-LDOBYP6)") (class "Default")
      (node (ref "C58") (pin "1") (pinfunction "1_1") (pintype "passive"))
      (node (ref "U1") (pin "46") (pinfunction "LDOBYP6_46") (pintype "passive"))
    )
    (net (code "84") (name "Net-(U1-LDOBYP7)") (class "Default")
      (node (ref "C59") (pin "1") (pinfunction "1_1") (pintype "passive"))
      (node (ref "U1") (pin "49") (pinfunction "LDOBYP7_49") (pintype "passive"))
    )
    (net (code "85") (name "Net-(Y1-OE)") (class "Default")
      (node (ref "JP4") (pin "2") (pinfunction "2_2") (pintype "passive"))
      (node (ref "Y1") (pin "2") (pinfunction "OE_2") (pintype "passive"))
    )
    (net (code "86") (name "Net-(Y1-V)") (class "Default")
      (node (ref "C19") (pin "1") (pinfunction "1_1") (pintype "passive"))
      (node (ref "C20") (pin "2") (pinfunction "2_2") (pintype "passive"))
      (node (ref "C21") (pin "2") (pinfunction "2_2") (pintype "passive"))
      (node (ref "C22") (pin "2") (pinfunction "2_2") (pintype "passive"))
      (node (ref "C23") (pin "2") (pinfunction "2_2") (pintype "passive"))
      (node (ref "FB6") (pin "2") (pinfunction "2_2") (pintype "passive"))
      (node (ref "JP4") (pin "1") (pinfunction "1_1") (pintype "passive"))
      (node (ref "Y1") (pin "6") (pinfunction "V_6") (pintype "power_in"))
    )
    (net (code "87") (name "Net-(Y2-OE)") (class "Default")
      (node (ref "JP5") (pin "3") (pinfunction "3_3") (pintype "passive"))
      (node (ref "Y2") (pin "2") (pinfunction "OE_2") (pintype "passive"))
    )
    (net (code "88") (name "Net-(Y2-OE1)") (class "Default")
      (node (ref "JP5") (pin "1") (pinfunction "1_1") (pintype "passive"))
      (node (ref "Y2") (pin "1") (pinfunction "OE1_1") (pintype "passive"))
    )
    (net (code "89") (name "Net-(Y2-V)") (class "Default")
      (node (ref "C45") (pin "1") (pinfunction "1_1") (pintype "passive"))
      (node (ref "C46") (pin "1") (pinfunction "1_1") (pintype "passive"))
      (node (ref "C47") (pin "2") (pinfunction "2_2") (pintype "passive"))
      (node (ref "FB12") (pin "2") (pinfunction "2_2") (pintype "passive"))
      (node (ref "Y2") (pin "6") (pinfunction "V_6") (pintype "power_in"))
    )
    (net (code "90") (name "VCK33") (class "Default")
      (node (ref "C32") (pin "1") (pinfunction "1_1") (pintype "passive"))
      (node (ref "C33") (pin "1") (pinfunction "1_1") (pintype "passive"))
      (node (ref "C34") (pin "1") (pinfunction "1_1") (pintype "passive"))
      (node (ref "C41") (pin "1") (pinfunction "1_1") (pintype "passive"))
      (node (ref "C42") (pin "1") (pinfunction "1_1") (pintype "passive"))
      (node (ref "C43") (pin "1") (pinfunction "1_1") (pintype "passive"))
      (node (ref "D1") (pin "1") (pinfunction "ANODE_1") (pintype "passive"))
      (node (ref "FB1") (pin "1") (pinfunction "1_1") (pintype "passive"))
      (node (ref "FB10") (pin "1") (pinfunction "1_1") (pintype "passive"))
      (node (ref "FB11") (pin "1") (pinfunction "1_1") (pintype "passive"))
      (node (ref "FB2") (pin "1") (pinfunction "1_1") (pintype "passive"))
      (node (ref "FB3") (pin "1") (pinfunction "1_1") (pintype "passive"))
      (node (ref "FB4") (pin "1") (pinfunction "1_1") (pintype "passive"))
      (node (ref "FB5") (pin "1") (pinfunction "1_1") (pintype "passive"))
      (node (ref "FB8") (pin "1") (pinfunction "1_1") (pintype "passive"))
      (node (ref "FB9") (pin "1") (pinfunction "1_1") (pintype "passive"))
    )
    (net (code "91") (name "VCKOSC") (class "Default")
      (node (ref "C24") (pin "1") (pinfunction "1_1") (pintype "passive"))
      (node (ref "C25") (pin "1") (pinfunction "1_1") (pintype "passive"))
      (node (ref "C26") (pin "1") (pinfunction "1_1") (pintype "passive"))
      (node (ref "FB8") (pin "2") (pinfunction "2_2") (pintype "passive"))
      (node (ref "U1") (pin "41") (pinfunction "VCC6_OSCOUT_41") (pintype "passive"))
    )
    (net (code "92") (name "VCKPLL1") (class "Default")
      (node (ref "C13") (pin "1") (pinfunction "1_1") (pintype "passive"))
      (node (ref "C14") (pin "1") (pinfunction "1_1") (pintype "passive"))
      (node (ref "C15") (pin "1") (pinfunction "1_1") (pintype "passive"))
      (node (ref "FB4") (pin "2") (pinfunction "2_2") (pintype "passive"))
      (node (ref "U1") (pin "38") (pinfunction "VCC5_PLL1_38") (pintype "passive"))
    )
    (net (code "93") (name "VCKPLL2") (class "Default")
      (node (ref "C35") (pin "1") (pinfunction "1_1") (pintype "passive"))
      (node (ref "C36") (pin "1") (pinfunction "1_1") (pintype "passive"))
      (node (ref "C37") (pin "1") (pinfunction "1_1") (pintype "passive"))
      (node (ref "FB10") (pin "2") (pinfunction "2_2") (pintype "passive"))
      (node (ref "U1") (pin "51") (pinfunction "VCC7_PLL2_51") (pintype "passive"))
    )
    (net (code "94") (name "VCKSR") (class "Default")
      (node (ref "C7") (pin "1") (pinfunction "1_1") (pintype "passive"))
      (node (ref "C8") (pin "1") (pinfunction "1_1") (pintype "passive"))
      (node (ref "C9") (pin "1") (pinfunction "1_1") (pintype "passive"))
      (node (ref "FB2") (pin "2") (pinfunction "2_2") (pintype "passive"))
      (node (ref "U1") (pin "21") (pinfunction "VCC3_SYSREF_21") (pintype "passive"))
    )
    (net (code "95") (name "VCKVCO") (class "Default")
      (node (ref "C3") (pin "1") (pinfunction "1_1") (pintype "passive"))
      (node (ref "C4") (pin "1") (pinfunction "1_1") (pintype "passive"))
      (node (ref "C5") (pin "1") (pinfunction "1_1") (pintype "passive"))
      (node (ref "FB1") (pin "2") (pinfunction "2_2") (pintype "passive"))
      (node (ref "U1") (pin "10") (pinfunction "VCC1_VCO_10") (pintype "passive"))
    )
    (net (code "96") (name "VHMC2") (class "Default")
      (node (ref "C10") (pin "1") (pinfunction "1_1") (pintype "passive"))
      (node (ref "C11") (pin "1") (pinfunction "1_1") (pintype "passive"))
      (node (ref "C12") (pin "1") (pinfunction "1_1") (pintype "passive"))
      (node (ref "FB3") (pin "2") (pinfunction "2_2") (pintype "passive"))
      (node (ref "U1") (pin "17") (pinfunction "VCC2_OUT_17") (pintype "passive"))
    )
    (net (code "97") (name "VHMC4") (class "Default")
      (node (ref "C27") (pin "1") (pinfunction "1_1") (pintype "passive"))
      (node (ref "C28") (pin "1") (pinfunction "1_1") (pintype "passive"))
      (node (ref "C29") (pin "1") (pinfunction "1_1") (pintype "passive"))
      (node (ref "FB9") (pin "2") (pinfunction "2_2") (pintype "passive"))
      (node (ref "U1") (pin "26") (pinfunction "VCC4_OUT_26") (pintype "passive"))
    )
    (net (code "98") (name "VHMC8") (class "Default")
      (node (ref "C38") (pin "1") (pinfunction "1_1") (pintype "passive"))
      (node (ref "C39") (pin "1") (pinfunction "1_1") (pintype "passive"))
      (node (ref "C40") (pin "1") (pinfunction "1_1") (pintype "passive"))
      (node (ref "FB11") (pin "2") (pinfunction "2_2") (pintype "passive"))
      (node (ref "U1") (pin "57") (pinfunction "VCC8_OUT_57") (pintype "passive"))
    )
    (net (code "99") (name "VHMC9") (class "Default")
      (node (ref "C16") (pin "1") (pinfunction "1_1") (pintype "passive"))
      (node (ref "C17") (pin "1") (pinfunction "1_1") (pintype "passive"))
      (node (ref "C18") (pin "1") (pinfunction "1_1") (pintype "passive"))
      (node (ref "FB5") (pin "2") (pinfunction "2_2") (pintype "passive"))
      (node (ref "U1") (pin "68") (pinfunction "VCC9_OUT_68") (pintype "passive"))
    )
    (net (code "100") (name "VOSC1") (class "Default")
      (node (ref "FB6") (pin "1") (pinfunction "1_1") (pintype "passive"))
    )
    (net (code "101") (name "VOSC2") (class "Default")
      (node (ref "FB12") (pin "1") (pinfunction "1_1") (pintype "passive"))
      (node (ref "JP5") (pin "2") (pinfunction "2_2") (pintype "passive"))
    )
    (net (code "102") (name "unconnected-(T1-NC-Pad5)") (class "Default")
      (node (ref "T1") (pin "5") (pinfunction "NC_5") (pintype "passive"))
    )
    (net (code "103") (name "unconnected-(U1-OSCOUT1_N-Pad45)") (class "Default")
      (node (ref "U1") (pin "45") (pinfunction "OSCOUT1_N_45") (pintype "passive+no_connect"))
    )
    (net (code "104") (name "unconnected-(U1-OSCOUT1_P-Pad44)") (class "Default")
      (node (ref "U1") (pin "44") (pinfunction "OSCOUT1_P_44") (pintype "passive+no_connect"))
    )
  )
)
